# support.net
KiCad netlist of a schematic drawn in Altium Designer
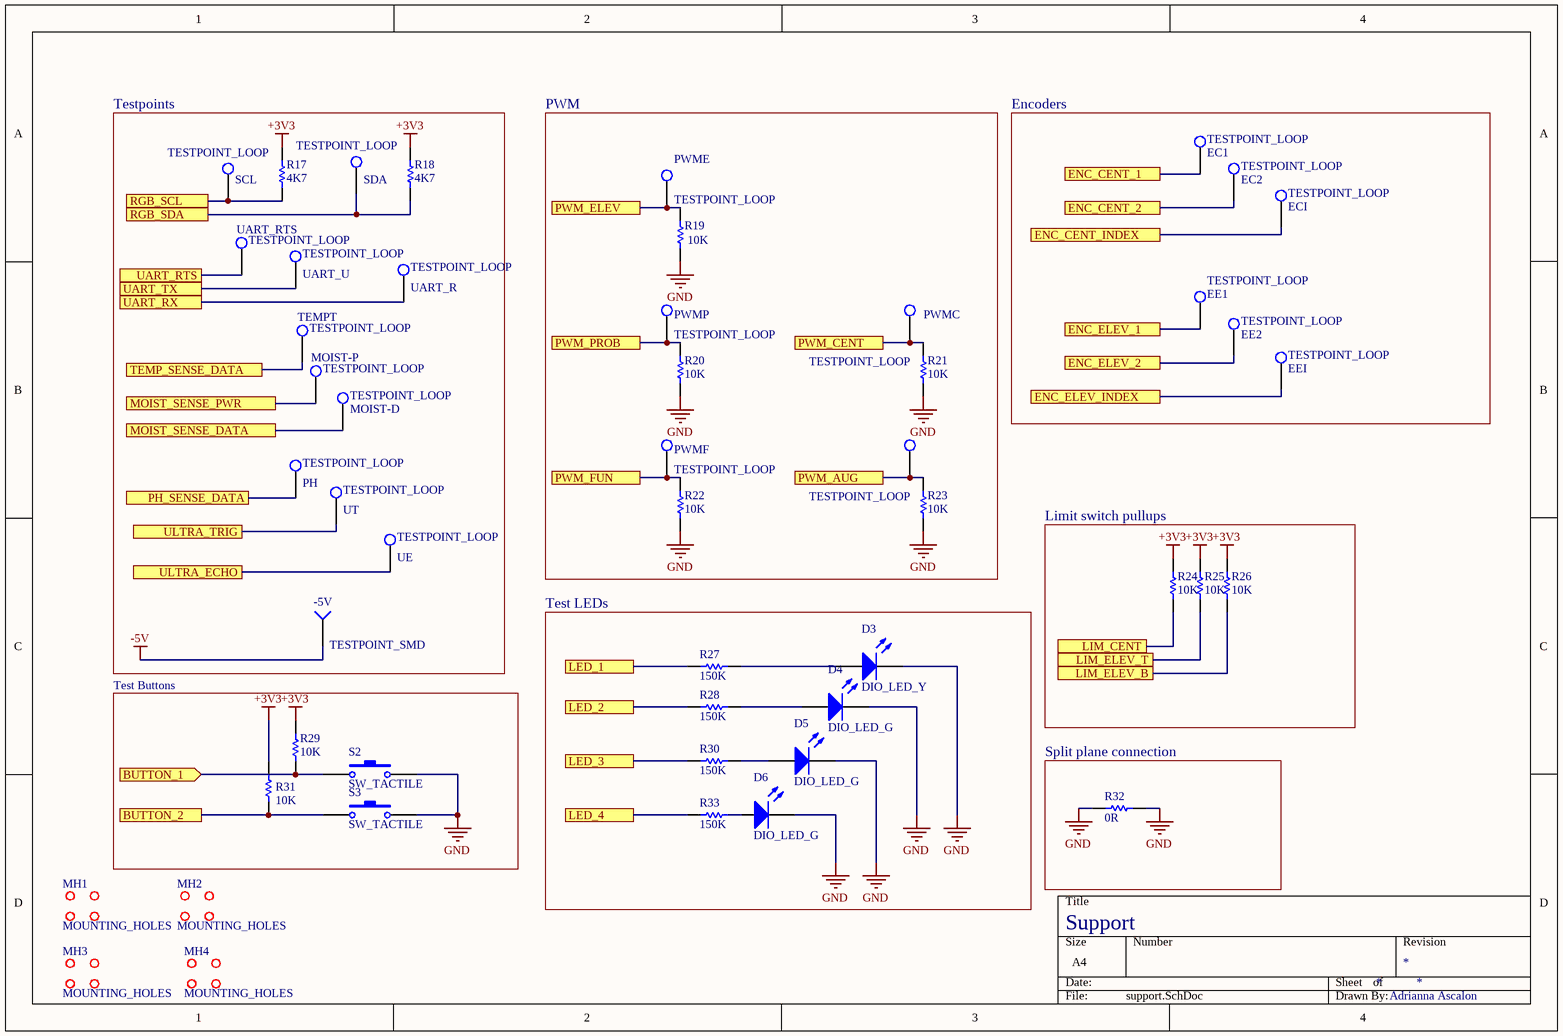
[diagram p0: support.SchDoc]

(export (version "E")
  (design (tool "Eeschema 10.0.6"))
  (components
    (comp (ref "-5V")
      (value "TESTPOINT_SMD")
      (footprint "TESTPOINT")
      (libsource (lib "UWRT_Schematic_Library_2019") (part "TESTPOINT_SMD"))
    )
    (comp (ref "D3")
      (value "DIO_LED_Y")
      (footprint "LED_0805_LINE")
      (description "LED YELLOW DIFFUSED 0805 SMD")
      (fields (field (name "PART NUMBER") "LY R976-PS-36") (field (name "MANUFACTURER") "OSRAM"))
      (libsource (lib "UWRT_Schematic_Library_2019") (part "DIO_LED_Y"))
    )
    (comp (ref "D4")
      (value "DIO_LED_G")
      (footprint "LED_0805_LINE")
      (description "LED GREEN DIFFUSED 0805 SMD")
      (fields (field (name "PART NUMBER") "LG R971-KN-1") (field (name "MANUFACTURER") "OSRAM"))
      (libsource (lib "UWRT_Schematic_Library_2019") (part "DIO_LED_G"))
    )
    (comp (ref "D5")
      (value "DIO_LED_G")
      (footprint "LED_0805_LINE")
      (description "LED GREEN DIFFUSED 0805 SMD")
      (fields (field (name "PART NUMBER") "LG R971-KN-1") (field (name "MANUFACTURER") "OSRAM"))
      (libsource (lib "UWRT_Schematic_Library_2019") (part "DIO_LED_G"))
    )
    (comp (ref "D6")
      (value "DIO_LED_G")
      (footprint "LED_0805_LINE")
      (description "LED GREEN DIFFUSED 0805 SMD")
      (fields (field (name "PART NUMBER") "LG R971-KN-1") (field (name "MANUFACTURER") "OSRAM"))
      (libsource (lib "UWRT_Schematic_Library_2019") (part "DIO_LED_G"))
    )
    (comp (ref "EC1")
      (value "TESTPOINT_LOOP")
      (footprint "TESTPOINT_LOOP")
      (libsource (lib "UWRT_Schematic_Library_2019") (part "TESTPOINT_LOOP"))
    )
    (comp (ref "EC2")
      (value "TESTPOINT_LOOP")
      (footprint "TESTPOINT_LOOP")
      (libsource (lib "UWRT_Schematic_Library_2019") (part "TESTPOINT_LOOP"))
    )
    (comp (ref "ECI")
      (value "TESTPOINT_LOOP")
      (footprint "TESTPOINT_LOOP")
      (libsource (lib "UWRT_Schematic_Library_2019") (part "TESTPOINT_LOOP"))
    )
    (comp (ref "EE1")
      (value "TESTPOINT_LOOP")
      (footprint "TESTPOINT_LOOP")
      (libsource (lib "UWRT_Schematic_Library_2019") (part "TESTPOINT_LOOP"))
    )
    (comp (ref "EE2")
      (value "TESTPOINT_LOOP")
      (footprint "TESTPOINT_LOOP")
      (libsource (lib "UWRT_Schematic_Library_2019") (part "TESTPOINT_LOOP"))
    )
    (comp (ref "EEI")
      (value "TESTPOINT_LOOP")
      (footprint "TESTPOINT_LOOP")
      (libsource (lib "UWRT_Schematic_Library_2019") (part "TESTPOINT_LOOP"))
    )
    (comp (ref "MH1")
      (value "MOUNTING_HOLES")
      (footprint "MOUNTING_HOLE")
      (description "6cm x 6cm")
      (libsource (lib "UWRT_Schematic_Library_2019") (part "MOUNTING_HOLES"))
    )
    (comp (ref "MH2")
      (value "MOUNTING_HOLES")
      (footprint "MOUNTING_HOLE")
      (description "6cm x 6cm")
      (libsource (lib "UWRT_Schematic_Library_2019") (part "MOUNTING_HOLES"))
    )
    (comp (ref "MH3")
      (value "MOUNTING_HOLES")
      (footprint "MOUNTING_HOLE")
      (description "6cm x 6cm")
      (libsource (lib "UWRT_Schematic_Library_2019") (part "MOUNTING_HOLES"))
    )
    (comp (ref "MH4")
      (value "MOUNTING_HOLES")
      (footprint "MOUNTING_HOLE")
      (description "6cm x 6cm")
      (libsource (lib "UWRT_Schematic_Library_2019") (part "MOUNTING_HOLES"))
    )
    (comp (ref "MOIST-D")
      (value "TESTPOINT_LOOP")
      (footprint "TESTPOINT_LOOP")
      (libsource (lib "UWRT_Schematic_Library_2019") (part "TESTPOINT_LOOP"))
    )
    (comp (ref "MOIST-P")
      (value "TESTPOINT_LOOP")
      (footprint "TESTPOINT_LOOP")
      (libsource (lib "UWRT_Schematic_Library_2019") (part "TESTPOINT_LOOP"))
    )
    (comp (ref "PH")
      (value "TESTPOINT_LOOP")
      (footprint "TESTPOINT_LOOP")
      (libsource (lib "UWRT_Schematic_Library_2019") (part "TESTPOINT_LOOP"))
    )
    (comp (ref "PWMA")
      (value "TESTPOINT_LOOP")
      (footprint "TESTPOINT_LOOP")
      (libsource (lib "UWRT_Schematic_Library_2019") (part "TESTPOINT_LOOP"))
    )
    (comp (ref "PWMC")
      (value "TESTPOINT_LOOP")
      (footprint "TESTPOINT_LOOP")
      (libsource (lib "UWRT_Schematic_Library_2019") (part "TESTPOINT_LOOP"))
    )
    (comp (ref "PWME")
      (value "TESTPOINT_LOOP")
      (footprint "TESTPOINT_LOOP")
      (libsource (lib "UWRT_Schematic_Library_2019") (part "TESTPOINT_LOOP"))
    )
    (comp (ref "PWMF")
      (value "TESTPOINT_LOOP")
      (footprint "TESTPOINT_LOOP")
      (libsource (lib "UWRT_Schematic_Library_2019") (part "TESTPOINT_LOOP"))
    )
    (comp (ref "PWMP")
      (value "TESTPOINT_LOOP")
      (footprint "TESTPOINT_LOOP")
      (libsource (lib "UWRT_Schematic_Library_2019") (part "TESTPOINT_LOOP"))
    )
    (comp (ref "R17")
      (value "4K7")
      (footprint "RESC0603(1608)_N")
      (description "RES SMD 4.7K OHM 5% 1/10W 0603")
      (fields (field (name "MANUFACTURER") "Yageo") (field (name "TOLERANCE") "5%"))
      (libsource (lib "UWRT_Schematic_Library_2019") (part "RES_4K7_0603"))
    )
    (comp (ref "R18")
      (value "4K7")
      (footprint "RESC0603(1608)_N")
      (description "RES SMD 4.7K OHM 5% 1/10W 0603")
      (fields (field (name "MANUFACTURER") "Yageo") (field (name "TOLERANCE") "5%"))
      (libsource (lib "UWRT_Schematic_Library_2019") (part "RES_4K7_0603"))
    )
    (comp (ref "R19")
      (value "10K")
      (footprint "RESC0603(1608)_N")
      (description "RES SMD 10K OHM 5% 1/10W 0603")
      (fields (field (name "MANUFACTURER") "Yageo") (field (name "TOLERANCE") "5%"))
      (libsource (lib "UWRT_Schematic_Library_2019") (part "RES_10K_0603"))
    )
    (comp (ref "R20")
      (value "10K")
      (footprint "RESC0603(1608)_N")
      (description "RES SMD 10K OHM 5% 1/10W 0603")
      (fields (field (name "MANUFACTURER") "Yageo") (field (name "TOLERANCE") "5%"))
      (libsource (lib "UWRT_Schematic_Library_2019") (part "RES_10K_0603"))
    )
    (comp (ref "R21")
      (value "10K")
      (footprint "RESC0603(1608)_N")
      (description "RES SMD 10K OHM 5% 1/10W 0603")
      (fields (field (name "MANUFACTURER") "Yageo") (field (name "TOLERANCE") "5%"))
      (libsource (lib "UWRT_Schematic_Library_2019") (part "RES_10K_0603"))
    )
    (comp (ref "R22")
      (value "10K")
      (footprint "RESC0603(1608)_N")
      (description "RES SMD 10K OHM 5% 1/10W 0603")
      (fields (field (name "MANUFACTURER") "Yageo") (field (name "TOLERANCE") "5%"))
      (libsource (lib "UWRT_Schematic_Library_2019") (part "RES_10K_0603"))
    )
    (comp (ref "R23")
      (value "10K")
      (footprint "RESC0603(1608)_N")
      (description "RES SMD 10K OHM 5% 1/10W 0603")
      (fields (field (name "MANUFACTURER") "Yageo") (field (name "TOLERANCE") "5%"))
      (libsource (lib "UWRT_Schematic_Library_2019") (part "RES_10K_0603"))
    )
    (comp (ref "R24")
      (value "10K")
      (footprint "RESC0603(1608)_N")
      (description "RES SMD 10K OHM 5% 1/10W 0603")
      (fields (field (name "MANUFACTURER") "Yageo") (field (name "TOLERANCE") "5%"))
      (libsource (lib "UWRT_Schematic_Library_2019") (part "RES_10K_0603"))
    )
    (comp (ref "R25")
      (value "10K")
      (footprint "RESC0603(1608)_N")
      (description "RES SMD 10K OHM 5% 1/10W 0603")
      (fields (field (name "MANUFACTURER") "Yageo") (field (name "TOLERANCE") "5%"))
      (libsource (lib "UWRT_Schematic_Library_2019") (part "RES_10K_0603"))
    )
    (comp (ref "R26")
      (value "10K")
      (footprint "RESC0603(1608)_N")
      (description "RES SMD 10K OHM 5% 1/10W 0603")
      (fields (field (name "MANUFACTURER") "Yageo") (field (name "TOLERANCE") "5%"))
      (libsource (lib "UWRT_Schematic_Library_2019") (part "RES_10K_0603"))
    )
    (comp (ref "R27")
      (value "150K")
      (footprint "RESC0603(1608)_N")
      (description "RES SMD 150K OHM 5% 1/10W 0603")
      (fields (field (name "MANUFACTURER") "Yageo") (field (name "TOLERANCE") "5%"))
      (libsource (lib "UWRT_Schematic_Library_2019") (part "RES_150K_0603"))
    )
    (comp (ref "R28")
      (value "150K")
      (footprint "RESC0603(1608)_N")
      (description "RES SMD 150K OHM 5% 1/10W 0603")
      (fields (field (name "MANUFACTURER") "Yageo") (field (name "TOLERANCE") "5%"))
      (libsource (lib "UWRT_Schematic_Library_2019") (part "RES_150K_0603"))
    )
    (comp (ref "R29")
      (value "10K")
      (footprint "RESC0603(1608)_N")
      (description "RES SMD 10K OHM 5% 1/10W 0603")
      (fields (field (name "MANUFACTURER") "Yageo") (field (name "TOLERANCE") "5%"))
      (libsource (lib "UWRT_Schematic_Library_2019") (part "RES_10K_0603"))
    )
    (comp (ref "R30")
      (value "150K")
      (footprint "RESC0603(1608)_N")
      (description "RES SMD 150K OHM 5% 1/10W 0603")
      (fields (field (name "MANUFACTURER") "Yageo") (field (name "TOLERANCE") "5%"))
      (libsource (lib "UWRT_Schematic_Library_2019") (part "RES_150K_0603"))
    )
    (comp (ref "R31")
      (value "10K")
      (footprint "RESC0603(1608)_N")
      (description "RES SMD 10K OHM 5% 1/10W 0603")
      (fields (field (name "MANUFACTURER") "Yageo") (field (name "TOLERANCE") "5%"))
      (libsource (lib "UWRT_Schematic_Library_2019") (part "RES_10K_0603"))
    )
    (comp (ref "R32")
      (value "0R")
      (footprint "RESC0603(1608)_N")
      (description "RES SMD 0 OHM JUMPER 1/10W 0603")
      (fields (field (name "MANUFACTURER") "Yageo") (field (name "Comment") "RES_0R_0603"))
      (libsource (lib "UWRT_Schematic_Library_2019") (part "RES_0R_0603"))
    )
    (comp (ref "R33")
      (value "150K")
      (footprint "RESC0603(1608)_N")
      (description "RES SMD 150K OHM 5% 1/10W 0603")
      (fields (field (name "MANUFACTURER") "Yageo") (field (name "TOLERANCE") "5%"))
      (libsource (lib "UWRT_Schematic_Library_2019") (part "RES_150K_0603"))
    )
    (comp (ref "S2")
      (value "SW_TACTILE")
      (footprint "B3U-1100P")
      (description "Tactile Switch (Grey)")
      (fields
        (field (name "MANUFACTURER PART NUMBER") "B3U-1100P")
        (field (name "DIGIKEY PART NUMBER") "SW1021TR-ND")
      )
      (libsource (lib "UWRT_Schematic_Library_2019") (part "SW_TACTILE"))
    )
    (comp (ref "S3")
      (value "SW_TACTILE")
      (footprint "B3U-1100P")
      (description "Tactile Switch (Grey)")
      (fields
        (field (name "MANUFACTURER PART NUMBER") "B3U-1100P")
        (field (name "DIGIKEY PART NUMBER") "SW1021TR-ND")
      )
      (libsource (lib "UWRT_Schematic_Library_2019") (part "SW_TACTILE"))
    )
    (comp (ref "SCL")
      (value "TESTPOINT_LOOP")
      (footprint "TESTPOINT_LOOP")
      (libsource (lib "UWRT_Schematic_Library_2019") (part "TESTPOINT_LOOP"))
    )
    (comp (ref "SDA")
      (value "TESTPOINT_LOOP")
      (footprint "TESTPOINT_LOOP")
      (libsource (lib "UWRT_Schematic_Library_2019") (part "TESTPOINT_LOOP"))
    )
    (comp (ref "TEMPT")
      (value "TESTPOINT_LOOP")
      (footprint "TESTPOINT_LOOP")
      (libsource (lib "UWRT_Schematic_Library_2019") (part "TESTPOINT_LOOP"))
    )
    (comp (ref "UART_R")
      (value "TESTPOINT_LOOP")
      (footprint "TESTPOINT_LOOP")
      (libsource (lib "UWRT_Schematic_Library_2019") (part "TESTPOINT_LOOP"))
    )
    (comp (ref "UART_RTS")
      (value "TESTPOINT_LOOP")
      (footprint "TESTPOINT_LOOP")
      (libsource (lib "UWRT_Schematic_Library_2019") (part "TESTPOINT_LOOP"))
    )
    (comp (ref "UART_U")
      (value "TESTPOINT_LOOP")
      (footprint "TESTPOINT_LOOP")
      (libsource (lib "UWRT_Schematic_Library_2019") (part "TESTPOINT_LOOP"))
    )
    (comp (ref "UE")
      (value "TESTPOINT_LOOP")
      (footprint "TESTPOINT_LOOP")
      (libsource (lib "UWRT_Schematic_Library_2019") (part "TESTPOINT_LOOP"))
    )
    (comp (ref "UT")
      (value "TESTPOINT_LOOP")
      (footprint "TESTPOINT_LOOP")
      (libsource (lib "UWRT_Schematic_Library_2019") (part "TESTPOINT_LOOP"))
    )
  )
  (nets
    (net (code "1") (name "+3V3") (class "Default")
      (node (ref "R17") (pin "2") (pinfunction "2_2") (pintype "passive"))
      (node (ref "R18") (pin "2") (pinfunction "2_2") (pintype "passive"))
      (node (ref "R24") (pin "2") (pinfunction "2_2") (pintype "passive"))
      (node (ref "R25") (pin "2") (pinfunction "2_2") (pintype "passive"))
      (node (ref "R26") (pin "2") (pinfunction "2_2") (pintype "passive"))
      (node (ref "R29") (pin "2") (pinfunction "2_2") (pintype "passive"))
      (node (ref "R31") (pin "1") (pinfunction "1_1") (pintype "passive"))
    )
    (net (code "2") (name "-5V") (class "Default")
      (node (ref "-5V") (pin "1") (pinfunction "=value_1") (pintype "passive"))
    )
    (net (code "3") (name "/BUTTON_1") (class "Default")
      (node (ref "R29") (pin "1") (pinfunction "1_1") (pintype "passive"))
      (node (ref "S2") (pin "1") (pinfunction "1_1") (pintype "passive"))
    )
    (net (code "4") (name "/BUTTON_2") (class "Default")
      (node (ref "R31") (pin "2") (pinfunction "2_2") (pintype "passive"))
      (node (ref "S3") (pin "1") (pinfunction "1_1") (pintype "passive"))
    )
    (net (code "5") (name "/ENC_CENT_1") (class "Default")
      (node (ref "EC1") (pin "1") (pinfunction "=value_1") (pintype "passive"))
    )
    (net (code "6") (name "/ENC_CENT_2") (class "Default")
      (node (ref "EC2") (pin "1") (pinfunction "=value_1") (pintype "passive"))
    )
    (net (code "7") (name "/ENC_CENT_INDEX") (class "Default")
      (node (ref "ECI") (pin "1") (pinfunction "=value_1") (pintype "passive"))
    )
    (net (code "8") (name "/ENC_ELEV_1") (class "Default")
      (node (ref "EE1") (pin "1") (pinfunction "=value_1") (pintype "passive"))
    )
    (net (code "9") (name "/ENC_ELEV_2") (class "Default")
      (node (ref "EE2") (pin "1") (pinfunction "=value_1") (pintype "passive"))
    )
    (net (code "10") (name "/ENC_ELEV_INDEX") (class "Default")
      (node (ref "EEI") (pin "1") (pinfunction "=value_1") (pintype "passive"))
    )
    (net (code "11") (name "/LED_1") (class "Default")
      (node (ref "R27") (pin "1") (pinfunction "1_1") (pintype "passive"))
    )
    (net (code "12") (name "/LED_2") (class "Default")
      (node (ref "R28") (pin "1") (pinfunction "1_1") (pintype "passive"))
    )
    (net (code "13") (name "/LED_3") (class "Default")
      (node (ref "R30") (pin "1") (pinfunction "1_1") (pintype "passive"))
    )
    (net (code "14") (name "/LED_4") (class "Default")
      (node (ref "R33") (pin "1") (pinfunction "1_1") (pintype "passive"))
    )
    (net (code "15") (name "/LIM_CENT") (class "Default")
      (node (ref "R24") (pin "1") (pinfunction "1_1") (pintype "passive"))
    )
    (net (code "16") (name "/LIM_ELEV_B") (class "Default")
      (node (ref "R26") (pin "1") (pinfunction "1_1") (pintype "passive"))
    )
    (net (code "17") (name "/LIM_ELEV_T") (class "Default")
      (node (ref "R25") (pin "1") (pinfunction "1_1") (pintype "passive"))
    )
    (net (code "18") (name "/MOIST_SENSE_DATA") (class "Default")
      (node (ref "MOIST-D") (pin "1") (pinfunction "=value_1") (pintype "passive"))
    )
    (net (code "19") (name "/MOIST_SENSE_PWR") (class "Default")
      (node (ref "MOIST-P") (pin "1") (pinfunction "=value_1") (pintype "passive"))
    )
    (net (code "20") (name "/PH_SENSE_DATA") (class "Default")
      (node (ref "PH") (pin "1") (pinfunction "=value_1") (pintype "passive"))
    )
    (net (code "21") (name "/PWM_AUG") (class "Default")
      (node (ref "PWMA") (pin "1") (pinfunction "=value_1") (pintype "passive"))
      (node (ref "R23") (pin "2") (pinfunction "2_2") (pintype "passive"))
    )
    (net (code "22") (name "/PWM_CENT") (class "Default")
      (node (ref "PWMC") (pin "1") (pinfunction "=value_1") (pintype "passive"))
      (node (ref "R21") (pin "2") (pinfunction "2_2") (pintype "passive"))
    )
    (net (code "23") (name "/PWM_ELEV") (class "Default")
      (node (ref "PWME") (pin "1") (pinfunction "=value_1") (pintype "passive"))
      (node (ref "R19") (pin "2") (pinfunction "2_2") (pintype "passive"))
    )
    (net (code "24") (name "/PWM_FUN") (class "Default")
      (node (ref "PWMF") (pin "1") (pinfunction "=value_1") (pintype "passive"))
      (node (ref "R22") (pin "2") (pinfunction "2_2") (pintype "passive"))
    )
    (net (code "25") (name "/PWM_PROB") (class "Default")
      (node (ref "PWMP") (pin "1") (pinfunction "=value_1") (pintype "passive"))
      (node (ref "R20") (pin "2") (pinfunction "2_2") (pintype "passive"))
    )
    (net (code "26") (name "/RGB_SCL") (class "Default")
      (node (ref "R17") (pin "1") (pinfunction "1_1") (pintype "passive"))
      (node (ref "SCL") (pin "1") (pinfunction "=value_1") (pintype "passive"))
    )
    (net (code "27") (name "/RGB_SDA") (class "Default")
      (node (ref "R18") (pin "1") (pinfunction "1_1") (pintype "passive"))
      (node (ref "SDA") (pin "1") (pinfunction "=value_1") (pintype "passive"))
    )
    (net (code "28") (name "/TEMP_SENSE_DATA") (class "Default")
      (node (ref "TEMPT") (pin "1") (pinfunction "=value_1") (pintype "passive"))
    )
    (net (code "29") (name "/UART_RTS") (class "Default")
      (node (ref "UART_RTS") (pin "1") (pinfunction "=value_1") (pintype "passive"))
    )
    (net (code "30") (name "/UART_RX") (class "Default")
      (node (ref "UART_R") (pin "1") (pinfunction "=value_1") (pintype "passive"))
    )
    (net (code "31") (name "/UART_TX") (class "Default")
      (node (ref "UART_U") (pin "1") (pinfunction "=value_1") (pintype "passive"))
    )
    (net (code "32") (name "/ULTRA_ECHO") (class "Default")
      (node (ref "UE") (pin "1") (pinfunction "=value_1") (pintype "passive"))
    )
    (net (code "33") (name "/ULTRA_TRIG") (class "Default")
      (node (ref "UT") (pin "1") (pinfunction "=value_1") (pintype "passive"))
    )
    (net (code "34") (name "GND") (class "Default")
      (node (ref "D3") (pin "2") (pinfunction "K_2") (pintype "passive"))
      (node (ref "D4") (pin "2") (pinfunction "K_2") (pintype "passive"))
      (node (ref "D5") (pin "2") (pinfunction "K_2") (pintype "passive"))
      (node (ref "D6") (pin "2") (pinfunction "K_2") (pintype "passive"))
      (node (ref "R19") (pin "1") (pinfunction "1_1") (pintype "passive"))
      (node (ref "R20") (pin "1") (pinfunction "1_1") (pintype "passive"))
      (node (ref "R21") (pin "1") (pinfunction "1_1") (pintype "passive"))
      (node (ref "R22") (pin "1") (pinfunction "1_1") (pintype "passive"))
      (node (ref "R23") (pin "1") (pinfunction "1_1") (pintype "passive"))
      (node (ref "R32") (pin "1") (pinfunction "1_1") (pintype "passive"))
      (node (ref "R32") (pin "2") (pinfunction "2_2") (pintype "passive"))
      (node (ref "S2") (pin "2") (pinfunction "2_2") (pintype "passive"))
      (node (ref "S3") (pin "2") (pinfunction "2_2") (pintype "passive"))
    )
    (net (code "35") (name "Net-(D3-A)") (class "Default")
      (node (ref "D3") (pin "1") (pinfunction "A_1") (pintype "passive"))
      (node (ref "R27") (pin "2") (pinfunction "2_2") (pintype "passive"))
    )
    (net (code "36") (name "Net-(D4-A)") (class "Default")
      (node (ref "D4") (pin "1") (pinfunction "A_1") (pintype "passive"))
      (node (ref "R28") (pin "2") (pinfunction "2_2") (pintype "passive"))
    )
    (net (code "37") (name "Net-(D5-A)") (class "Default")
      (node (ref "D5") (pin "1") (pinfunction "A_1") (pintype "passive"))
      (node (ref "R30") (pin "2") (pinfunction "2_2") (pintype "passive"))
    )
    (net (code "38") (name "Net-(D6-A)") (class "Default")
      (node (ref "D6") (pin "1") (pinfunction "A_1") (pintype "passive"))
      (node (ref "R33") (pin "2") (pinfunction "2_2") (pintype "passive"))
    )
  )
)
